# BurnWireTimer.net
KiCad netlist of a schematic drawn in EAGLE
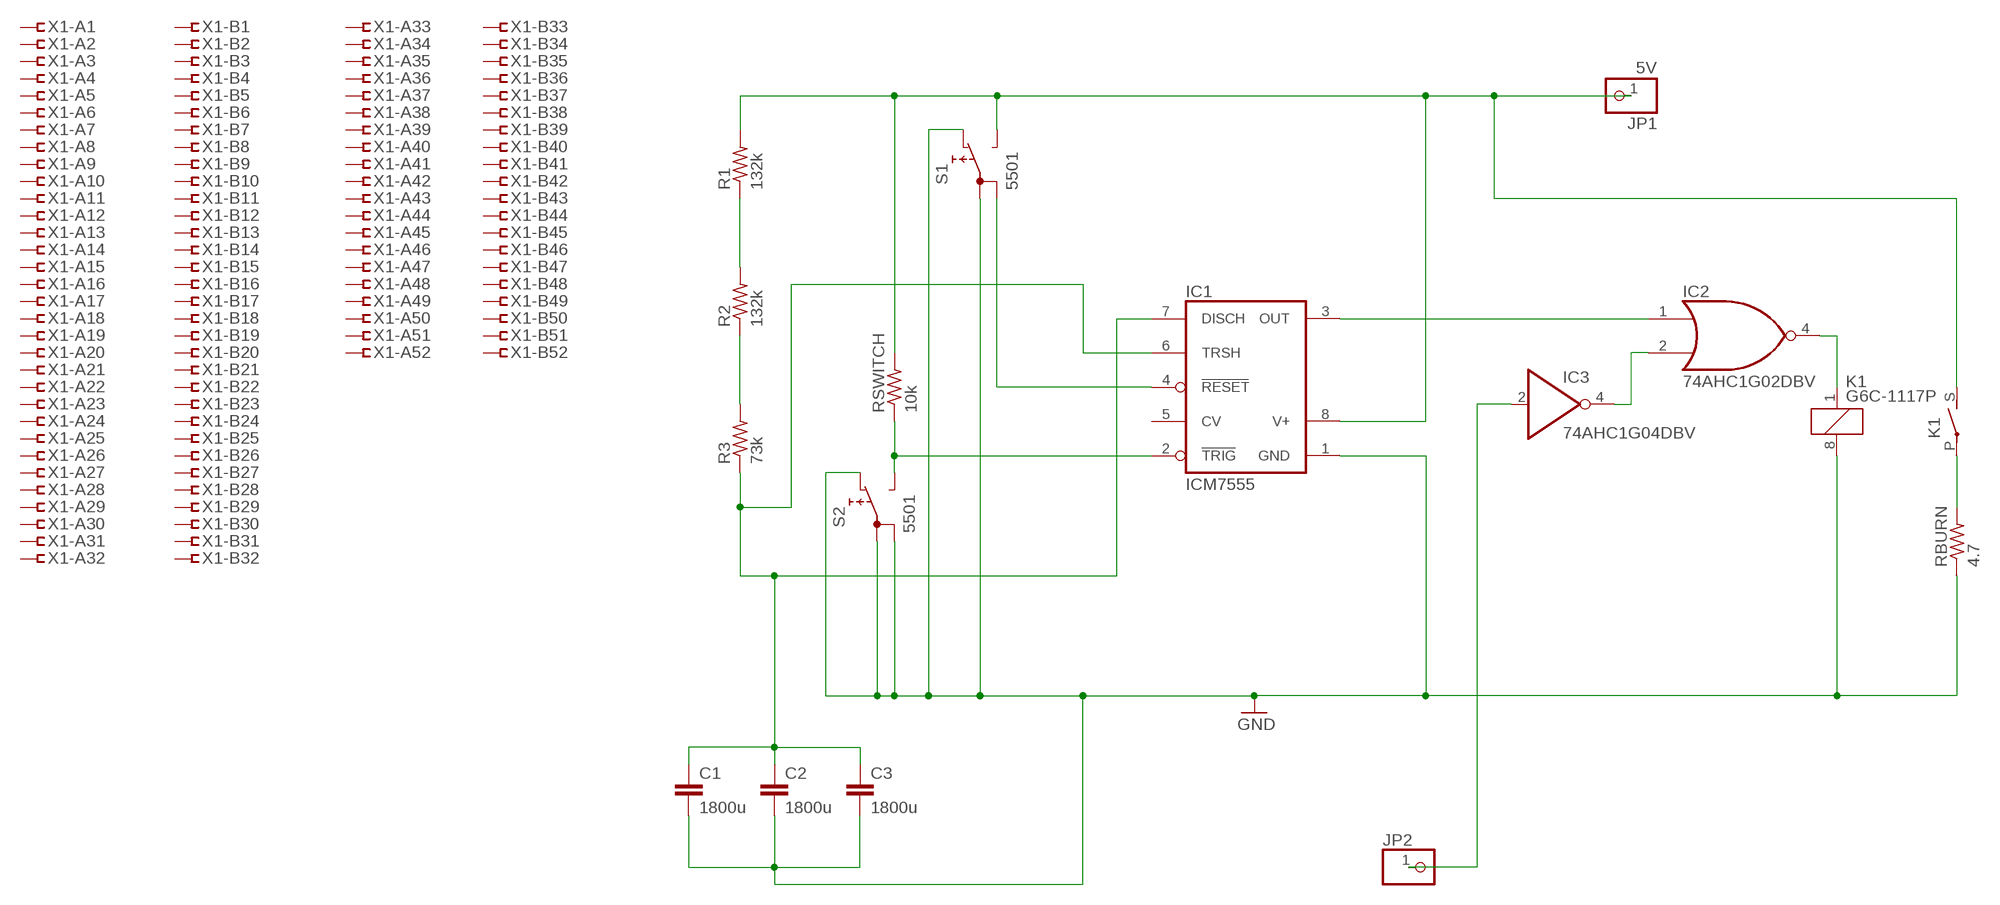
[diagram p0: schematic, sheet 1]

(export (version "E")
  (design (tool "Eeschema 10.0.6"))
  (components
    (comp (ref "C1")
      (value "1800u")
      (footprint "eagle-import:C5B3")
      (libsource (lib "eagle-import") (part "C5/3"))
    )
    (comp (ref "C2")
      (value "1800u")
      (footprint "eagle-import:C5B3")
      (libsource (lib "eagle-import") (part "C5/3"))
    )
    (comp (ref "C3")
      (value "1800u")
      (footprint "eagle-import:C5B3")
      (libsource (lib "eagle-import") (part "C5/3"))
    )
    (comp (ref "IC1")
      (value "ICM7555")
      (footprint "eagle-import:DIL08")
      (fields (field (name "MF") "MAXIM") (field (name "MPN") "ICM7555IPA+"))
      (libsource (lib "eagle-import") (part "ICM7555"))
    )
    (comp (ref "IC2")
      (value "74AHC1G02DBV")
      (footprint "eagle-import:SOT23-5")
      (libsource (lib "eagle-import") (part "741G02DBVAHC"))
    )
    (comp (ref "IC3")
      (value "74AHC1G04DBV")
      (footprint "eagle-import:SOT23-5")
      (libsource (lib "eagle-import") (part "741G04DBVAHC"))
    )
    (comp (ref "JP1")
      (value "5V")
      (footprint "eagle-import:1X01")
      (libsource (lib "eagle-import") (part "PINHD-1X1"))
    )
    (comp (ref "JP2")
      (value "PINHD-1X1")
      (footprint "eagle-import:1X01")
      (libsource (lib "eagle-import") (part "PINHD-1X1"))
    )
    (comp (ref "K1")
      (value "G6C-1117P")
      (footprint "eagle-import:G6C-1117P")
      (libsource (lib "eagle-import") (part "G6C-1117P"))
    )
    (comp (ref "R1")
      (value "132k")
      (footprint "eagle-import:0309_10")
      (libsource (lib "eagle-import") (part "R-US_0309/10"))
    )
    (comp (ref "R2")
      (value "132k")
      (footprint "eagle-import:0309_10")
      (libsource (lib "eagle-import") (part "R-US_0309/10"))
    )
    (comp (ref "R3")
      (value "73k")
      (footprint "eagle-import:0309_10")
      (libsource (lib "eagle-import") (part "R-US_0309/10"))
    )
    (comp (ref "RBURN")
      (value "4.7")
      (footprint "eagle-import:0309_10")
      (libsource (lib "eagle-import") (part "R-US_0309/10"))
    )
    (comp (ref "RSWITCH")
      (value "10k")
      (footprint "eagle-import:0309_10")
      (libsource (lib "eagle-import") (part "R-US_0309/10"))
    )
    (comp (ref "S1")
      (value "5501")
      (footprint "eagle-import:5501")
      (libsource (lib "eagle-import") (part "55?01"))
    )
    (comp (ref "S2")
      (value "5501")
      (footprint "eagle-import:5501")
      (libsource (lib "eagle-import") (part "55?01"))
    )
    (comp (ref "X1")
      (value "1184C")
      (footprint "eagle-import:1184C")
      (libsource (lib "eagle-import") (part "1184C"))
    )
  )
  (nets
    (net (code "1") (name "GND") (class "Default")
      (node (ref "C1") (pin "2") (pinfunction "2_2") (pintype "passive"))
      (node (ref "C2") (pin "2") (pinfunction "2_2") (pintype "passive"))
      (node (ref "C3") (pin "2") (pinfunction "2_2") (pintype "passive"))
      (node (ref "IC1") (pin "1") (pinfunction "GND_1") (pintype "power_in"))
      (node (ref "K1") (pin "8") (pinfunction "2_8") (pintype "passive"))
      (node (ref "RBURN") (pin "1") (pinfunction "1_1") (pintype "passive"))
      (node (ref "S1") (pin "1A") (pinfunction "1A_1A") (pintype "passive"))
      (node (ref "S1") (pin "NC") (pinfunction "NC_NC") (pintype "passive"))
      (node (ref "S2") (pin "1A") (pinfunction "1A_1A") (pintype "passive"))
      (node (ref "S2") (pin "1B") (pinfunction "1B_1B") (pintype "passive"))
      (node (ref "S2") (pin "NC") (pinfunction "NC_NC") (pintype "passive"))
    )
    (net (code "2") (name "Net-(IC1-DISCH)") (class "Default")
      (node (ref "C1") (pin "1") (pinfunction "1_1") (pintype "passive"))
      (node (ref "C2") (pin "1") (pinfunction "1_1") (pintype "passive"))
      (node (ref "C3") (pin "1") (pinfunction "1_1") (pintype "passive"))
      (node (ref "IC1") (pin "6") (pinfunction "TRSH_6") (pintype "input"))
      (node (ref "IC1") (pin "7") (pinfunction "DISCH_7") (pintype "input"))
      (node (ref "R3") (pin "1") (pinfunction "1_1") (pintype "passive"))
    )
    (net (code "3") (name "Net-(IC1-OUT)") (class "Default")
      (node (ref "IC1") (pin "3") (pinfunction "OUT_3") (pintype "output"))
      (node (ref "IC2") (pin "1") (pinfunction "I0_1") (pintype "input"))
    )
    (net (code "4") (name "Net-(IC1-RESET)") (class "Default")
      (node (ref "IC1") (pin "4") (pinfunction "RESET_4") (pintype "input"))
      (node (ref "S1") (pin "1B") (pinfunction "1B_1B") (pintype "passive"))
    )
    (net (code "5") (name "Net-(IC1-TRIG)") (class "Default")
      (node (ref "IC1") (pin "2") (pinfunction "TRIG_2") (pintype "bidirectional"))
      (node (ref "RSWITCH") (pin "1") (pinfunction "1_1") (pintype "passive"))
      (node (ref "S2") (pin "NO") (pinfunction "NO_NO") (pintype "passive"))
    )
    (net (code "6") (name "Net-(IC1-V+)") (class "Default")
      (node (ref "IC1") (pin "8") (pinfunction "V+_8") (pintype "power_in"))
      (node (ref "JP1") (pin "1") (pinfunction "1_1") (pintype "passive"))
      (node (ref "K1") (pin "S") (pinfunction "S_S") (pintype "passive"))
      (node (ref "R1") (pin "2") (pinfunction "2_2") (pintype "passive"))
      (node (ref "RSWITCH") (pin "2") (pinfunction "2_2") (pintype "passive"))
      (node (ref "S1") (pin "NO") (pinfunction "NO_NO") (pintype "passive"))
    )
    (net (code "7") (name "Net-(IC2A-I1)") (class "Default")
      (node (ref "IC2") (pin "2") (pinfunction "I1_2") (pintype "input"))
      (node (ref "IC3") (pin "4") (pinfunction "O_4") (pintype "output"))
    )
    (net (code "8") (name "Net-(IC2A-O)") (class "Default")
      (node (ref "IC2") (pin "4") (pinfunction "O_4") (pintype "output"))
      (node (ref "K1") (pin "1") (pinfunction "1_1") (pintype "passive"))
    )
    (net (code "9") (name "Net-(IC3A-I)") (class "Default")
      (node (ref "IC3") (pin "2") (pinfunction "I_2") (pintype "input"))
      (node (ref "JP2") (pin "1") (pinfunction "1_1") (pintype "passive"))
    )
    (net (code "10") (name "Net-(K1-PadP)") (class "Default")
      (node (ref "K1") (pin "P") (pinfunction "P_P") (pintype "passive"))
      (node (ref "RBURN") (pin "2") (pinfunction "2_2") (pintype "passive"))
    )
    (net (code "11") (name "Net-(R1-Pad1)") (class "Default")
      (node (ref "R1") (pin "1") (pinfunction "1_1") (pintype "passive"))
      (node (ref "R2") (pin "2") (pinfunction "2_2") (pintype "passive"))
    )
    (net (code "12") (name "Net-(R2-Pad1)") (class "Default")
      (node (ref "R2") (pin "1") (pinfunction "1_1") (pintype "passive"))
      (node (ref "R3") (pin "2") (pinfunction "2_2") (pintype "passive"))
    )
    (net (code "13") (name "unconnected-(IC1-CV-Pad5)") (class "Default")
      (node (ref "IC1") (pin "5") (pinfunction "CV_5") (pintype "passive"))
    )
    (net (code "14") (name "unconnected-(X1A-1-PadA1)") (class "Default")
      (node (ref "X1") (pin "A1") (pinfunction "1_A1") (pintype "passive"))
    )
    (net (code "15") (name "unconnected-(X1AA-1-PadA33)") (class "Default")
      (node (ref "X1") (pin "A33") (pinfunction "1_A33") (pintype "passive"))
    )
    (net (code "16") (name "unconnected-(X1AB-1-PadA34)") (class "Default")
      (node (ref "X1") (pin "A34") (pinfunction "1_A34") (pintype "passive"))
    )
    (net (code "17") (name "unconnected-(X1AC-1-PadA35)") (class "Default")
      (node (ref "X1") (pin "A35") (pinfunction "1_A35") (pintype "passive"))
    )
    (net (code "18") (name "unconnected-(X1AD-1-PadA36)") (class "Default")
      (node (ref "X1") (pin "A36") (pinfunction "1_A36") (pintype "passive"))
    )
    (net (code "19") (name "unconnected-(X1AE-1-PadA37)") (class "Default")
      (node (ref "X1") (pin "A37") (pinfunction "1_A37") (pintype "passive"))
    )
    (net (code "20") (name "unconnected-(X1AF-1-PadA38)") (class "Default")
      (node (ref "X1") (pin "A38") (pinfunction "1_A38") (pintype "passive"))
    )
    (net (code "21") (name "unconnected-(X1AG-1-PadA39)") (class "Default")
      (node (ref "X1") (pin "A39") (pinfunction "1_A39") (pintype "passive"))
    )
    (net (code "22") (name "unconnected-(X1AH-1-PadA4)") (class "Default")
      (node (ref "X1") (pin "A4") (pinfunction "1_A4") (pintype "passive"))
    )
    (net (code "23") (name "unconnected-(X1AI-1-PadA40)") (class "Default")
      (node (ref "X1") (pin "A40") (pinfunction "1_A40") (pintype "passive"))
    )
    (net (code "24") (name "unconnected-(X1AJ-1-PadA41)") (class "Default")
      (node (ref "X1") (pin "A41") (pinfunction "1_A41") (pintype "passive"))
    )
    (net (code "25") (name "unconnected-(X1AK-1-PadA42)") (class "Default")
      (node (ref "X1") (pin "A42") (pinfunction "1_A42") (pintype "passive"))
    )
    (net (code "26") (name "unconnected-(X1AL-1-PadA43)") (class "Default")
      (node (ref "X1") (pin "A43") (pinfunction "1_A43") (pintype "passive"))
    )
    (net (code "27") (name "unconnected-(X1AM-1-PadA44)") (class "Default")
      (node (ref "X1") (pin "A44") (pinfunction "1_A44") (pintype "passive"))
    )
    (net (code "28") (name "unconnected-(X1AN-1-PadA45)") (class "Default")
      (node (ref "X1") (pin "A45") (pinfunction "1_A45") (pintype "passive"))
    )
    (net (code "29") (name "unconnected-(X1AO-1-PadA46)") (class "Default")
      (node (ref "X1") (pin "A46") (pinfunction "1_A46") (pintype "passive"))
    )
    (net (code "30") (name "unconnected-(X1AP-1-PadA47)") (class "Default")
      (node (ref "X1") (pin "A47") (pinfunction "1_A47") (pintype "passive"))
    )
    (net (code "31") (name "unconnected-(X1AQ-1-PadA48)") (class "Default")
      (node (ref "X1") (pin "A48") (pinfunction "1_A48") (pintype "passive"))
    )
    (net (code "32") (name "unconnected-(X1AR-1-PadA49)") (class "Default")
      (node (ref "X1") (pin "A49") (pinfunction "1_A49") (pintype "passive"))
    )
    (net (code "33") (name "unconnected-(X1AS-1-PadA5)") (class "Default")
      (node (ref "X1") (pin "A5") (pinfunction "1_A5") (pintype "passive"))
    )
    (net (code "34") (name "unconnected-(X1AT-1-PadA50)") (class "Default")
      (node (ref "X1") (pin "A50") (pinfunction "1_A50") (pintype "passive"))
    )
    (net (code "35") (name "unconnected-(X1AU-1-PadA51)") (class "Default")
      (node (ref "X1") (pin "A51") (pinfunction "1_A51") (pintype "passive"))
    )
    (net (code "36") (name "unconnected-(X1AV-1-PadA52)") (class "Default")
      (node (ref "X1") (pin "A52") (pinfunction "1_A52") (pintype "passive"))
    )
    (net (code "37") (name "unconnected-(X1AW-1-PadA6)") (class "Default")
      (node (ref "X1") (pin "A6") (pinfunction "1_A6") (pintype "passive"))
    )
    (net (code "38") (name "unconnected-(X1AX-1-PadA7)") (class "Default")
      (node (ref "X1") (pin "A7") (pinfunction "1_A7") (pintype "passive"))
    )
    (net (code "39") (name "unconnected-(X1AY-1-PadA8)") (class "Default")
      (node (ref "X1") (pin "A8") (pinfunction "1_A8") (pintype "passive"))
    )
    (net (code "40") (name "unconnected-(X1AZ-1-PadA9)") (class "Default")
      (node (ref "X1") (pin "A9") (pinfunction "1_A9") (pintype "passive"))
    )
    (net (code "41") (name "unconnected-(X1B-1-PadA10)") (class "Default")
      (node (ref "X1") (pin "A10") (pinfunction "1_A10") (pintype "passive"))
    )
    (net (code "42") (name "unconnected-(X1BA-1-PadB1)") (class "Default")
      (node (ref "X1") (pin "B1") (pinfunction "1_B1") (pintype "passive"))
    )
    (net (code "43") (name "unconnected-(X1BB-1-PadB10)") (class "Default")
      (node (ref "X1") (pin "B10") (pinfunction "1_B10") (pintype "passive"))
    )
    (net (code "44") (name "unconnected-(X1BC-1-PadB11)") (class "Default")
      (node (ref "X1") (pin "B11") (pinfunction "1_B11") (pintype "passive"))
    )
    (net (code "45") (name "unconnected-(X1BD-1-PadB12)") (class "Default")
      (node (ref "X1") (pin "B12") (pinfunction "1_B12") (pintype "passive"))
    )
    (net (code "46") (name "unconnected-(X1BE-1-PadB13)") (class "Default")
      (node (ref "X1") (pin "B13") (pinfunction "1_B13") (pintype "passive"))
    )
    (net (code "47") (name "unconnected-(X1BF-1-PadB14)") (class "Default")
      (node (ref "X1") (pin "B14") (pinfunction "1_B14") (pintype "passive"))
    )
    (net (code "48") (name "unconnected-(X1BG-1-PadB15)") (class "Default")
      (node (ref "X1") (pin "B15") (pinfunction "1_B15") (pintype "passive"))
    )
    (net (code "49") (name "unconnected-(X1BH-1-PadB16)") (class "Default")
      (node (ref "X1") (pin "B16") (pinfunction "1_B16") (pintype "passive"))
    )
    (net (code "50") (name "unconnected-(X1BI-1-PadB17)") (class "Default")
      (node (ref "X1") (pin "B17") (pinfunction "1_B17") (pintype "passive"))
    )
    (net (code "51") (name "unconnected-(X1BJ-1-PadB18)") (class "Default")
      (node (ref "X1") (pin "B18") (pinfunction "1_B18") (pintype "passive"))
    )
    (net (code "52") (name "unconnected-(X1BK-1-PadB19)") (class "Default")
      (node (ref "X1") (pin "B19") (pinfunction "1_B19") (pintype "passive"))
    )
    (net (code "53") (name "unconnected-(X1BL-1-PadB2)") (class "Default")
      (node (ref "X1") (pin "B2") (pinfunction "1_B2") (pintype "passive"))
    )
    (net (code "54") (name "unconnected-(X1BM-1-PadB20)") (class "Default")
      (node (ref "X1") (pin "B20") (pinfunction "1_B20") (pintype "passive"))
    )
    (net (code "55") (name "unconnected-(X1BN-1-PadB21)") (class "Default")
      (node (ref "X1") (pin "B21") (pinfunction "1_B21") (pintype "passive"))
    )
    (net (code "56") (name "unconnected-(X1BO-1-PadB22)") (class "Default")
      (node (ref "X1") (pin "B22") (pinfunction "1_B22") (pintype "passive"))
    )
    (net (code "57") (name "unconnected-(X1BP-1-PadB23)") (class "Default")
      (node (ref "X1") (pin "B23") (pinfunction "1_B23") (pintype "passive"))
    )
    (net (code "58") (name "unconnected-(X1BQ-1-PadB24)") (class "Default")
      (node (ref "X1") (pin "B24") (pinfunction "1_B24") (pintype "passive"))
    )
    (net (code "59") (name "unconnected-(X1BR-1-PadB25)") (class "Default")
      (node (ref "X1") (pin "B25") (pinfunction "1_B25") (pintype "passive"))
    )
    (net (code "60") (name "unconnected-(X1BS-1-PadB26)") (class "Default")
      (node (ref "X1") (pin "B26") (pinfunction "1_B26") (pintype "passive"))
    )
    (net (code "61") (name "unconnected-(X1BT-1-PadB27)") (class "Default")
      (node (ref "X1") (pin "B27") (pinfunction "1_B27") (pintype "passive"))
    )
    (net (code "62") (name "unconnected-(X1BU-1-PadB28)") (class "Default")
      (node (ref "X1") (pin "B28") (pinfunction "1_B28") (pintype "passive"))
    )
    (net (code "63") (name "unconnected-(X1BV-1-PadB29)") (class "Default")
      (node (ref "X1") (pin "B29") (pinfunction "1_B29") (pintype "passive"))
    )
    (net (code "64") (name "unconnected-(X1BW-1-PadB3)") (class "Default")
      (node (ref "X1") (pin "B3") (pinfunction "1_B3") (pintype "passive"))
    )
    (net (code "65") (name "unconnected-(X1BX-1-PadB30)") (class "Default")
      (node (ref "X1") (pin "B30") (pinfunction "1_B30") (pintype "passive"))
    )
    (net (code "66") (name "unconnected-(X1BY-1-PadB31)") (class "Default")
      (node (ref "X1") (pin "B31") (pinfunction "1_B31") (pintype "passive"))
    )
    (net (code "67") (name "unconnected-(X1BZ-1-PadB32)") (class "Default")
      (node (ref "X1") (pin "B32") (pinfunction "1_B32") (pintype "passive"))
    )
    (net (code "68") (name "unconnected-(X1C-1-PadA11)") (class "Default")
      (node (ref "X1") (pin "A11") (pinfunction "1_A11") (pintype "passive"))
    )
    (net (code "69") (name "unconnected-(X1CA-1-PadB33)") (class "Default")
      (node (ref "X1") (pin "B33") (pinfunction "1_B33") (pintype "passive"))
    )
    (net (code "70") (name "unconnected-(X1CB-1-PadB34)") (class "Default")
      (node (ref "X1") (pin "B34") (pinfunction "1_B34") (pintype "passive"))
    )
    (net (code "71") (name "unconnected-(X1CC-1-PadB35)") (class "Default")
      (node (ref "X1") (pin "B35") (pinfunction "1_B35") (pintype "passive"))
    )
    (net (code "72") (name "unconnected-(X1CD-1-PadB36)") (class "Default")
      (node (ref "X1") (pin "B36") (pinfunction "1_B36") (pintype "passive"))
    )
    (net (code "73") (name "unconnected-(X1CE-1-PadB37)") (class "Default")
      (node (ref "X1") (pin "B37") (pinfunction "1_B37") (pintype "passive"))
    )
    (net (code "74") (name "unconnected-(X1CF-1-PadB38)") (class "Default")
      (node (ref "X1") (pin "B38") (pinfunction "1_B38") (pintype "passive"))
    )
    (net (code "75") (name "unconnected-(X1CG-1-PadB39)") (class "Default")
      (node (ref "X1") (pin "B39") (pinfunction "1_B39") (pintype "passive"))
    )
    (net (code "76") (name "unconnected-(X1CH-1-PadB4)") (class "Default")
      (node (ref "X1") (pin "B4") (pinfunction "1_B4") (pintype "passive"))
    )
    (net (code "77") (name "unconnected-(X1CI-1-PadB40)") (class "Default")
      (node (ref "X1") (pin "B40") (pinfunction "1_B40") (pintype "passive"))
    )
    (net (code "78") (name "unconnected-(X1CJ-1-PadB41)") (class "Default")
      (node (ref "X1") (pin "B41") (pinfunction "1_B41") (pintype "passive"))
    )
    (net (code "79") (name "unconnected-(X1CK-1-PadB42)") (class "Default")
      (node (ref "X1") (pin "B42") (pinfunction "1_B42") (pintype "passive"))
    )
    (net (code "80") (name "unconnected-(X1CL-1-PadB43)") (class "Default")
      (node (ref "X1") (pin "B43") (pinfunction "1_B43") (pintype "passive"))
    )
    (net (code "81") (name "unconnected-(X1CM-1-PadB44)") (class "Default")
      (node (ref "X1") (pin "B44") (pinfunction "1_B44") (pintype "passive"))
    )
    (net (code "82") (name "unconnected-(X1CN-1-PadB45)") (class "Default")
      (node (ref "X1") (pin "B45") (pinfunction "1_B45") (pintype "passive"))
    )
    (net (code "83") (name "unconnected-(X1CO-1-PadB46)") (class "Default")
      (node (ref "X1") (pin "B46") (pinfunction "1_B46") (pintype "passive"))
    )
    (net (code "84") (name "unconnected-(X1CP-1-PadB47)") (class "Default")
      (node (ref "X1") (pin "B47") (pinfunction "1_B47") (pintype "passive"))
    )
    (net (code "85") (name "unconnected-(X1CQ-1-PadB48)") (class "Default")
      (node (ref "X1") (pin "B48") (pinfunction "1_B48") (pintype "passive"))
    )
    (net (code "86") (name "unconnected-(X1CR-1-PadB49)") (class "Default")
      (node (ref "X1") (pin "B49") (pinfunction "1_B49") (pintype "passive"))
    )
    (net (code "87") (name "unconnected-(X1CS-1-PadB5)") (class "Default")
      (node (ref "X1") (pin "B5") (pinfunction "1_B5") (pintype "passive"))
    )
    (net (code "88") (name "unconnected-(X1CT-1-PadB50)") (class "Default")
      (node (ref "X1") (pin "B50") (pinfunction "1_B50") (pintype "passive"))
    )
    (net (code "89") (name "unconnected-(X1CU-1-PadB51)") (class "Default")
      (node (ref "X1") (pin "B51") (pinfunction "1_B51") (pintype "passive"))
    )
    (net (code "90") (name "unconnected-(X1CV-1-PadB52)") (class "Default")
      (node (ref "X1") (pin "B52") (pinfunction "1_B52") (pintype "passive"))
    )
    (net (code "91") (name "unconnected-(X1CW-1-PadB6)") (class "Default")
      (node (ref "X1") (pin "B6") (pinfunction "1_B6") (pintype "passive"))
    )
    (net (code "92") (name "unconnected-(X1CX-1-PadB7)") (class "Default")
      (node (ref "X1") (pin "B7") (pinfunction "1_B7") (pintype "passive"))
    )
    (net (code "93") (name "unconnected-(X1CY-1-PadB8)") (class "Default")
      (node (ref "X1") (pin "B8") (pinfunction "1_B8") (pintype "passive"))
    )
    (net (code "94") (name "unconnected-(X1CZ-1-PadB9)") (class "Default")
      (node (ref "X1") (pin "B9") (pinfunction "1_B9") (pintype "passive"))
    )
    (net (code "95") (name "unconnected-(X1D-1-PadA12)") (class "Default")
      (node (ref "X1") (pin "A12") (pinfunction "1_A12") (pintype "passive"))
    )
    (net (code "96") (name "unconnected-(X1E-1-PadA13)") (class "Default")
      (node (ref "X1") (pin "A13") (pinfunction "1_A13") (pintype "passive"))
    )
    (net (code "97") (name "unconnected-(X1F-1-PadA14)") (class "Default")
      (node (ref "X1") (pin "A14") (pinfunction "1_A14") (pintype "passive"))
    )
    (net (code "98") (name "unconnected-(X1G-1-PadA15)") (class "Default")
      (node (ref "X1") (pin "A15") (pinfunction "1_A15") (pintype "passive"))
    )
    (net (code "99") (name "unconnected-(X1H-1-PadA16)") (class "Default")
      (node (ref "X1") (pin "A16") (pinfunction "1_A16") (pintype "passive"))
    )
    (net (code "100") (name "unconnected-(X1I-1-PadA17)") (class "Default")
      (node (ref "X1") (pin "A17") (pinfunction "1_A17") (pintype "passive"))
    )
    (net (code "101") (name "unconnected-(X1J-1-PadA18)") (class "Default")
      (node (ref "X1") (pin "A18") (pinfunction "1_A18") (pintype "passive"))
    )
    (net (code "102") (name "unconnected-(X1K-1-PadA19)") (class "Default")
      (node (ref "X1") (pin "A19") (pinfunction "1_A19") (pintype "passive"))
    )
    (net (code "103") (name "unconnected-(X1L-1-PadA2)") (class "Default")
      (node (ref "X1") (pin "A2") (pinfunction "1_A2") (pintype "passive"))
    )
    (net (code "104") (name "unconnected-(X1M-1-PadA20)") (class "Default")
      (node (ref "X1") (pin "A20") (pinfunction "1_A20") (pintype "passive"))
    )
    (net (code "105") (name "unconnected-(X1N-1-PadA21)") (class "Default")
      (node (ref "X1") (pin "A21") (pinfunction "1_A21") (pintype "passive"))
    )
    (net (code "106") (name "unconnected-(X1O-1-PadA22)") (class "Default")
      (node (ref "X1") (pin "A22") (pinfunction "1_A22") (pintype "passive"))
    )
    (net (code "107") (name "unconnected-(X1P-1-PadA23)") (class "Default")
      (node (ref "X1") (pin "A23") (pinfunction "1_A23") (pintype "passive"))
    )
    (net (code "108") (name "unconnected-(X1Q-1-PadA24)") (class "Default")
      (node (ref "X1") (pin "A24") (pinfunction "1_A24") (pintype "passive"))
    )
    (net (code "109") (name "unconnected-(X1R-1-PadA25)") (class "Default")
      (node (ref "X1") (pin "A25") (pinfunction "1_A25") (pintype "passive"))
    )
    (net (code "110") (name "unconnected-(X1S-1-PadA26)") (class "Default")
      (node (ref "X1") (pin "A26") (pinfunction "1_A26") (pintype "passive"))
    )
    (net (code "111") (name "unconnected-(X1T-1-PadA27)") (class "Default")
      (node (ref "X1") (pin "A27") (pinfunction "1_A27") (pintype "passive"))
    )
    (net (code "112") (name "unconnected-(X1U-1-PadA28)") (class "Default")
      (node (ref "X1") (pin "A28") (pinfunction "1_A28") (pintype "passive"))
    )
    (net (code "113") (name "unconnected-(X1V-1-PadA29)") (class "Default")
      (node (ref "X1") (pin "A29") (pinfunction "1_A29") (pintype "passive"))
    )
    (net (code "114") (name "unconnected-(X1W-1-PadA3)") (class "Default")
      (node (ref "X1") (pin "A3") (pinfunction "1_A3") (pintype "passive"))
    )
    (net (code "115") (name "unconnected-(X1X-1-PadA30)") (class "Default")
      (node (ref "X1") (pin "A30") (pinfunction "1_A30") (pintype "passive"))
    )
    (net (code "116") (name "unconnected-(X1Y-1-PadA31)") (class "Default")
      (node (ref "X1") (pin "A31") (pinfunction "1_A31") (pintype "passive"))
    )
    (net (code "117") (name "unconnected-(X1Z-1-PadA32)") (class "Default")
      (node (ref "X1") (pin "A32") (pinfunction "1_A32") (pintype "passive"))
    )
  )
)
